# DriverModuleQT.net
KiCad netlist of a schematic drawn in EAGLE
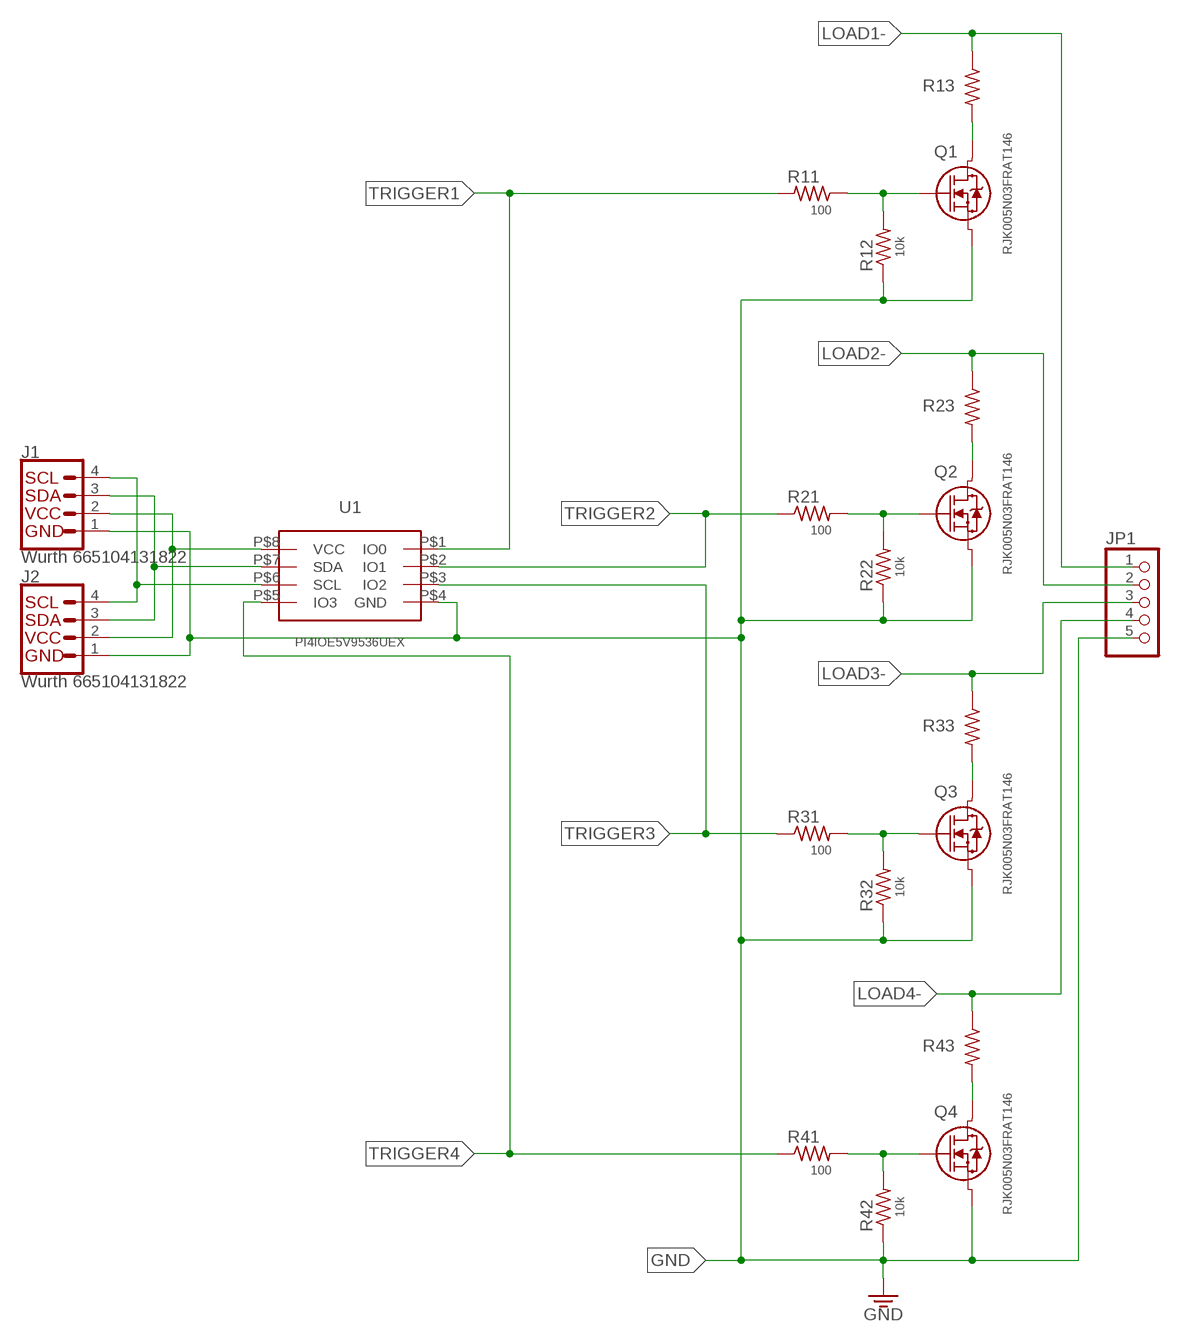
[diagram p0: schematic, sheet 1]

(export (version "E")
  (design (tool "Eeschema 10.0.6"))
  (components
    (comp (ref "J1")
      (value "Wurth 665104131822")
      (footprint "eagle-import:1X04_1MM_RA")
      (libsource (lib "eagle-import") (part "QWIIC_CONNECTORJS-1MM"))
    )
    (comp (ref "J2")
      (value "Wurth 665104131822")
      (footprint "eagle-import:1X04_1MM_RA")
      (libsource (lib "eagle-import") (part "QWIIC_CONNECTORJS-1MM"))
    )
    (comp (ref "JP1")
      (value "HEADER-1X576MIL")
      (footprint "eagle-import:1X05_ROUND_76")
      (libsource (lib "eagle-import") (part "HEADER-1X576MIL"))
    )
    (comp (ref "Q1")
      (value "RJK005N03FRAT146")
      (footprint "eagle-import:TRANS_RHK003N_ROM-M")
      (fields (field (name "COPYRIGHT") "Copyright (C) 2022 Ultra Librarian. All rights reserved."))
      (libsource (lib "eagle-import") (part "RJK005N03FRAT146TRANS_RHK003N_ROM-M"))
    )
    (comp (ref "Q2")
      (value "RJK005N03FRAT146")
      (footprint "eagle-import:TRANS_RHK003N_ROM-M")
      (fields (field (name "COPYRIGHT") "Copyright (C) 2022 Ultra Librarian. All rights reserved."))
      (libsource (lib "eagle-import") (part "RJK005N03FRAT146TRANS_RHK003N_ROM-M"))
    )
    (comp (ref "Q3")
      (value "RJK005N03FRAT146")
      (footprint "eagle-import:TRANS_RHK003N_ROM-M")
      (fields (field (name "COPYRIGHT") "Copyright (C) 2022 Ultra Librarian. All rights reserved."))
      (libsource (lib "eagle-import") (part "RJK005N03FRAT146TRANS_RHK003N_ROM-M"))
    )
    (comp (ref "Q4")
      (value "RJK005N03FRAT146")
      (footprint "eagle-import:TRANS_RHK003N_ROM-M")
      (fields (field (name "COPYRIGHT") "Copyright (C) 2022 Ultra Librarian. All rights reserved."))
      (libsource (lib "eagle-import") (part "RJK005N03FRAT146TRANS_RHK003N_ROM-M"))
    )
    (comp (ref "R11")
      (value "100")
      (footprint "eagle-import:R0603")
      (libsource (lib "eagle-import") (part "R-US_R0603"))
    )
    (comp (ref "R12")
      (value "10k")
      (footprint "eagle-import:R0603")
      (libsource (lib "eagle-import") (part "R-US_R0603"))
    )
    (comp (ref "R13")
      (value "R-US_R1206")
      (footprint "eagle-import:R1206")
      (libsource (lib "eagle-import") (part "R-US_R1206"))
    )
    (comp (ref "R21")
      (value "100")
      (footprint "eagle-import:R0603")
      (libsource (lib "eagle-import") (part "R-US_R0603"))
    )
    (comp (ref "R22")
      (value "10k")
      (footprint "eagle-import:R0603")
      (libsource (lib "eagle-import") (part "R-US_R0603"))
    )
    (comp (ref "R23")
      (value "R-US_R1206")
      (footprint "eagle-import:R1206")
      (libsource (lib "eagle-import") (part "R-US_R1206"))
    )
    (comp (ref "R31")
      (value "100")
      (footprint "eagle-import:R0603")
      (libsource (lib "eagle-import") (part "R-US_R0603"))
    )
    (comp (ref "R32")
      (value "10k")
      (footprint "eagle-import:R0603")
      (libsource (lib "eagle-import") (part "R-US_R0603"))
    )
    (comp (ref "R33")
      (value "R-US_R1206")
      (footprint "eagle-import:R1206")
      (libsource (lib "eagle-import") (part "R-US_R1206"))
    )
    (comp (ref "R41")
      (value "100")
      (footprint "eagle-import:R0603")
      (libsource (lib "eagle-import") (part "R-US_R0603"))
    )
    (comp (ref "R42")
      (value "10k")
      (footprint "eagle-import:R0603")
      (libsource (lib "eagle-import") (part "R-US_R0603"))
    )
    (comp (ref "R43")
      (value "R-US_R1206")
      (footprint "eagle-import:R1206")
      (libsource (lib "eagle-import") (part "R-US_R1206"))
    )
    (comp (ref "U1")
      (value "PI4IOE5V9536UEX")
      (footprint "eagle-import:MSOP-8")
      (libsource (lib "eagle-import") (part "PI4IOE5V9536-UEX"))
    )
  )
  (nets
    (net (code "1") (name "GND") (class "Default")
      (node (ref "J1") (pin "1") (pinfunction "GND_1") (pintype "power_in"))
      (node (ref "J2") (pin "1") (pinfunction "GND_1") (pintype "power_in"))
      (node (ref "JP1") (pin "5") (pinfunction "5_5") (pintype "passive"))
      (node (ref "Q1") (pin "3") (pinfunction "3_3") (pintype "passive"))
      (node (ref "Q2") (pin "3") (pinfunction "3_3") (pintype "passive"))
      (node (ref "Q3") (pin "3") (pinfunction "3_3") (pintype "passive"))
      (node (ref "Q4") (pin "3") (pinfunction "3_3") (pintype "passive"))
      (node (ref "R12") (pin "1") (pinfunction "1_1") (pintype "passive"))
      (node (ref "R22") (pin "1") (pinfunction "1_1") (pintype "passive"))
      (node (ref "R32") (pin "1") (pinfunction "1_1") (pintype "passive"))
      (node (ref "R42") (pin "1") (pinfunction "1_1") (pintype "passive"))
      (node (ref "U1") (pin "P$4") (pinfunction "GND_P$4") (pintype "bidirectional"))
    )
    (net (code "2") (name "LOAD1-") (class "Default")
      (node (ref "JP1") (pin "1") (pinfunction "1_1") (pintype "passive"))
      (node (ref "R13") (pin "1") (pinfunction "1_1") (pintype "passive"))
    )
    (net (code "3") (name "LOAD2-") (class "Default")
      (node (ref "JP1") (pin "2") (pinfunction "2_2") (pintype "passive"))
      (node (ref "R23") (pin "1") (pinfunction "1_1") (pintype "passive"))
    )
    (net (code "4") (name "LOAD3-") (class "Default")
      (node (ref "JP1") (pin "3") (pinfunction "3_3") (pintype "passive"))
      (node (ref "R33") (pin "1") (pinfunction "1_1") (pintype "passive"))
    )
    (net (code "5") (name "LOAD4-") (class "Default")
      (node (ref "JP1") (pin "4") (pinfunction "4_4") (pintype "passive"))
      (node (ref "R43") (pin "1") (pinfunction "1_1") (pintype "passive"))
    )
    (net (code "6") (name "Net-(J1-SCL)") (class "Default")
      (node (ref "J1") (pin "4") (pinfunction "SCL_4") (pintype "passive"))
      (node (ref "J2") (pin "4") (pinfunction "SCL_4") (pintype "passive"))
      (node (ref "U1") (pin "P$6") (pinfunction "SCL_P$6") (pintype "bidirectional"))
    )
    (net (code "7") (name "Net-(J1-SDA)") (class "Default")
      (node (ref "J1") (pin "3") (pinfunction "SDA_3") (pintype "passive"))
      (node (ref "J2") (pin "3") (pinfunction "SDA_3") (pintype "passive"))
      (node (ref "U1") (pin "P$7") (pinfunction "SDA_P$7") (pintype "bidirectional"))
    )
    (net (code "8") (name "Net-(J1-VCC)") (class "Default")
      (node (ref "J1") (pin "2") (pinfunction "VCC_2") (pintype "power_in"))
      (node (ref "J2") (pin "2") (pinfunction "VCC_2") (pintype "power_in"))
      (node (ref "U1") (pin "P$8") (pinfunction "VCC_P$8") (pintype "bidirectional"))
    )
    (net (code "9") (name "Net-(Q1-1)") (class "Default")
      (node (ref "Q1") (pin "2") (pinfunction "1_2") (pintype "passive"))
      (node (ref "R11") (pin "1") (pinfunction "1_1") (pintype "passive"))
      (node (ref "R12") (pin "2") (pinfunction "2_2") (pintype "passive"))
    )
    (net (code "10") (name "Net-(Q1-2)") (class "Default")
      (node (ref "Q1") (pin "1") (pinfunction "2_1") (pintype "passive"))
      (node (ref "R13") (pin "2") (pinfunction "2_2") (pintype "passive"))
    )
    (net (code "11") (name "Net-(Q2-1)") (class "Default")
      (node (ref "Q2") (pin "2") (pinfunction "1_2") (pintype "passive"))
      (node (ref "R21") (pin "2") (pinfunction "2_2") (pintype "passive"))
      (node (ref "R22") (pin "2") (pinfunction "2_2") (pintype "passive"))
    )
    (net (code "12") (name "Net-(Q2-2)") (class "Default")
      (node (ref "Q2") (pin "1") (pinfunction "2_1") (pintype "passive"))
      (node (ref "R23") (pin "2") (pinfunction "2_2") (pintype "passive"))
    )
    (net (code "13") (name "Net-(Q3-1)") (class "Default")
      (node (ref "Q3") (pin "2") (pinfunction "1_2") (pintype "passive"))
      (node (ref "R31") (pin "2") (pinfunction "2_2") (pintype "passive"))
      (node (ref "R32") (pin "2") (pinfunction "2_2") (pintype "passive"))
    )
    (net (code "14") (name "Net-(Q3-2)") (class "Default")
      (node (ref "Q3") (pin "1") (pinfunction "2_1") (pintype "passive"))
      (node (ref "R33") (pin "2") (pinfunction "2_2") (pintype "passive"))
    )
    (net (code "15") (name "Net-(Q4-1)") (class "Default")
      (node (ref "Q4") (pin "2") (pinfunction "1_2") (pintype "passive"))
      (node (ref "R41") (pin "2") (pinfunction "2_2") (pintype "passive"))
      (node (ref "R42") (pin "2") (pinfunction "2_2") (pintype "passive"))
    )
    (net (code "16") (name "Net-(Q4-2)") (class "Default")
      (node (ref "Q4") (pin "1") (pinfunction "2_1") (pintype "passive"))
      (node (ref "R43") (pin "2") (pinfunction "2_2") (pintype "passive"))
    )
    (net (code "17") (name "TRIGGER1") (class "Default")
      (node (ref "R11") (pin "2") (pinfunction "2_2") (pintype "passive"))
      (node (ref "U1") (pin "P$1") (pinfunction "IO0_P$1") (pintype "bidirectional"))
    )
    (net (code "18") (name "TRIGGER2") (class "Default")
      (node (ref "R21") (pin "1") (pinfunction "1_1") (pintype "passive"))
      (node (ref "U1") (pin "P$2") (pinfunction "IO1_P$2") (pintype "bidirectional"))
    )
    (net (code "19") (name "TRIGGER3") (class "Default")
      (node (ref "R31") (pin "1") (pinfunction "1_1") (pintype "passive"))
      (node (ref "U1") (pin "P$3") (pinfunction "IO2_P$3") (pintype "bidirectional"))
    )
    (net (code "20") (name "TRIGGER4") (class "Default")
      (node (ref "R41") (pin "1") (pinfunction "1_1") (pintype "passive"))
      (node (ref "U1") (pin "P$5") (pinfunction "IO3_P$5") (pintype "bidirectional"))
    )
  )
)
